# vga_ambilight_throughhole.net
KiCad netlist of a schematic drawn in EAGLE
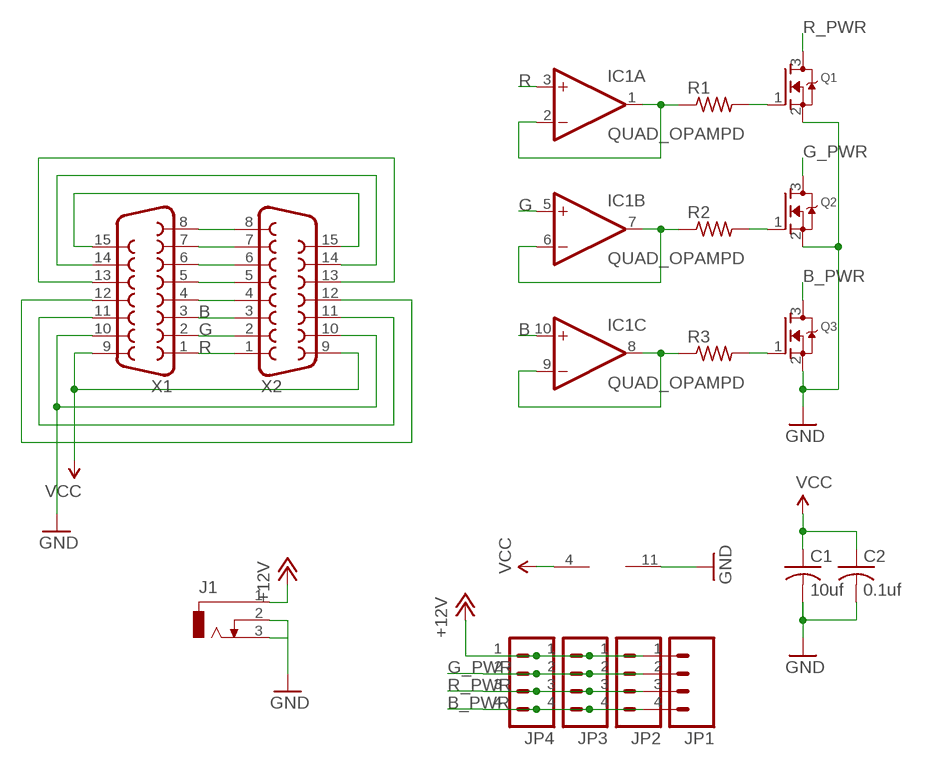
[diagram p0: schematic, sheet 1]

(export (version "E")
  (design (tool "Eeschema 10.0.6"))
  (components
    (comp (ref "C1")
      (value "10uf")
      (footprint "eagle-import:C1206")
      (libsource (lib "eagle-import") (part "C-USC1206"))
    )
    (comp (ref "C2")
      (value "0.1uf")
      (footprint "eagle-import:C1206")
      (libsource (lib "eagle-import") (part "C-USC1206"))
    )
    (comp (ref "IC1")
      (value "QUAD_OPAMPD")
      (footprint "eagle-import:SO14")
      (libsource (lib "eagle-import") (part "QUAD_OPAMPD"))
    )
    (comp (ref "J1")
      (value "DCJ0303")
      (footprint "eagle-import:DCJ0303")
      (libsource (lib "eagle-import") (part "DCJ0303"))
    )
    (comp (ref "JP1")
      (value "M04PTH")
      (footprint "eagle-import:1X04")
      (libsource (lib "eagle-import") (part "M04PTH"))
    )
    (comp (ref "JP2")
      (value "M04PTH")
      (footprint "eagle-import:1X04")
      (libsource (lib "eagle-import") (part "M04PTH"))
    )
    (comp (ref "JP3")
      (value "M04PTH")
      (footprint "eagle-import:1X04")
      (libsource (lib "eagle-import") (part "M04PTH"))
    )
    (comp (ref "JP4")
      (value "M04PTH")
      (footprint "eagle-import:1X04")
      (libsource (lib "eagle-import") (part "M04PTH"))
    )
    (comp (ref "Q1")
      (value "MOSFET-NREFLOW")
      (footprint "eagle-import:SOT23")
      (libsource (lib "eagle-import") (part "MOSFET-NREFLOW"))
    )
    (comp (ref "Q2")
      (value "MOSFET-NREFLOW")
      (footprint "eagle-import:SOT23")
      (libsource (lib "eagle-import") (part "MOSFET-NREFLOW"))
    )
    (comp (ref "Q3")
      (value "MOSFET-NREFLOW")
      (footprint "eagle-import:SOT23")
      (libsource (lib "eagle-import") (part "MOSFET-NREFLOW"))
    )
    (comp (ref "R1")
      (value "R-US_M0805")
      (footprint "eagle-import:M0805")
      (libsource (lib "eagle-import") (part "R-US_M0805"))
    )
    (comp (ref "R2")
      (value "R-US_M0805")
      (footprint "eagle-import:M0805")
      (libsource (lib "eagle-import") (part "R-US_M0805"))
    )
    (comp (ref "R3")
      (value "R-US_M0805")
      (footprint "eagle-import:M0805")
      (libsource (lib "eagle-import") (part "R-US_M0805"))
    )
    (comp (ref "X1")
      (value "F15HP")
      (footprint "eagle-import:F15HP")
      (libsource (lib "eagle-import") (part "F15HP"))
    )
    (comp (ref "X2")
      (value "F15HP")
      (footprint "eagle-import:F15HP")
      (libsource (lib "eagle-import") (part "F15HP"))
    )
  )
  (nets
    (net (code "1") (name "+12V") (class "Default")
      (node (ref "J1") (pin "1") (pinfunction "1_1") (pintype "passive"))
      (node (ref "JP1") (pin "1") (pinfunction "1_1") (pintype "passive"))
      (node (ref "JP2") (pin "1") (pinfunction "1_1") (pintype "passive"))
      (node (ref "JP3") (pin "1") (pinfunction "1_1") (pintype "passive"))
      (node (ref "JP4") (pin "1") (pinfunction "1_1") (pintype "passive"))
    )
    (net (code "2") (name "/B") (class "Default")
      (node (ref "IC1") (pin "10") (pinfunction "+IN_10") (pintype "input"))
      (node (ref "X1") (pin "3") (pinfunction "3_3") (pintype "passive"))
      (node (ref "X2") (pin "3") (pinfunction "3_3") (pintype "passive"))
    )
    (net (code "3") (name "/B_PWR") (class "Default")
      (node (ref "JP1") (pin "4") (pinfunction "4_4") (pintype "passive"))
      (node (ref "JP2") (pin "4") (pinfunction "4_4") (pintype "passive"))
      (node (ref "JP3") (pin "4") (pinfunction "4_4") (pintype "passive"))
      (node (ref "JP4") (pin "4") (pinfunction "4_4") (pintype "passive"))
      (node (ref "Q3") (pin "3") (pinfunction "D_3") (pintype "bidirectional"))
    )
    (net (code "4") (name "/G") (class "Default")
      (node (ref "IC1") (pin "5") (pinfunction "+IN_5") (pintype "input"))
      (node (ref "X1") (pin "2") (pinfunction "2_2") (pintype "passive"))
      (node (ref "X2") (pin "2") (pinfunction "2_2") (pintype "passive"))
    )
    (net (code "5") (name "/G_PWR") (class "Default")
      (node (ref "JP1") (pin "2") (pinfunction "2_2") (pintype "passive"))
      (node (ref "JP2") (pin "2") (pinfunction "2_2") (pintype "passive"))
      (node (ref "JP3") (pin "2") (pinfunction "2_2") (pintype "passive"))
      (node (ref "JP4") (pin "2") (pinfunction "2_2") (pintype "passive"))
      (node (ref "Q2") (pin "3") (pinfunction "D_3") (pintype "bidirectional"))
    )
    (net (code "6") (name "/R") (class "Default")
      (node (ref "IC1") (pin "3") (pinfunction "+IN_3") (pintype "input"))
      (node (ref "X1") (pin "1") (pinfunction "1_1") (pintype "passive"))
      (node (ref "X2") (pin "1") (pinfunction "1_1") (pintype "passive"))
    )
    (net (code "7") (name "/R_PWR") (class "Default")
      (node (ref "JP1") (pin "3") (pinfunction "3_3") (pintype "passive"))
      (node (ref "JP2") (pin "3") (pinfunction "3_3") (pintype "passive"))
      (node (ref "JP3") (pin "3") (pinfunction "3_3") (pintype "passive"))
      (node (ref "JP4") (pin "3") (pinfunction "3_3") (pintype "passive"))
      (node (ref "Q1") (pin "3") (pinfunction "D_3") (pintype "bidirectional"))
    )
    (net (code "8") (name "GND") (class "Default")
      (node (ref "C1") (pin "2") (pinfunction "2_2") (pintype "passive"))
      (node (ref "C2") (pin "2") (pinfunction "2_2") (pintype "passive"))
      (node (ref "IC1") (pin "11") (pinfunction "V-_11") (pintype "power_in"))
      (node (ref "J1") (pin "2") (pinfunction "2_2") (pintype "passive"))
      (node (ref "J1") (pin "3") (pinfunction "3_3") (pintype "passive"))
      (node (ref "Q1") (pin "2") (pinfunction "S_2") (pintype "bidirectional"))
      (node (ref "Q2") (pin "2") (pinfunction "S_2") (pintype "bidirectional"))
      (node (ref "Q3") (pin "2") (pinfunction "S_2") (pintype "bidirectional"))
      (node (ref "X1") (pin "10") (pinfunction "10_10") (pintype "passive"))
      (node (ref "X2") (pin "10") (pinfunction "10_10") (pintype "passive"))
    )
    (net (code "9") (name "Net-(IC1A--IN)") (class "Default")
      (node (ref "IC1") (pin "1") (pinfunction "OUT_1") (pintype "output"))
      (node (ref "IC1") (pin "2") (pinfunction "-IN_2") (pintype "input"))
      (node (ref "R1") (pin "1") (pinfunction "1_1") (pintype "passive"))
    )
    (net (code "10") (name "Net-(IC1B--IN)") (class "Default")
      (node (ref "IC1") (pin "6") (pinfunction "-IN_6") (pintype "input"))
      (node (ref "IC1") (pin "7") (pinfunction "OUT_7") (pintype "output"))
      (node (ref "R2") (pin "1") (pinfunction "1_1") (pintype "passive"))
    )
    (net (code "11") (name "Net-(IC1C--IN)") (class "Default")
      (node (ref "IC1") (pin "8") (pinfunction "OUT_8") (pintype "output"))
      (node (ref "IC1") (pin "9") (pinfunction "-IN_9") (pintype "input"))
      (node (ref "R3") (pin "1") (pinfunction "1_1") (pintype "passive"))
    )
    (net (code "12") (name "Net-(Q1-G)") (class "Default")
      (node (ref "Q1") (pin "1") (pinfunction "G_1") (pintype "bidirectional"))
      (node (ref "R1") (pin "2") (pinfunction "2_2") (pintype "passive"))
    )
    (net (code "13") (name "Net-(Q2-G)") (class "Default")
      (node (ref "Q2") (pin "1") (pinfunction "G_1") (pintype "bidirectional"))
      (node (ref "R2") (pin "2") (pinfunction "2_2") (pintype "passive"))
    )
    (net (code "14") (name "Net-(Q3-G)") (class "Default")
      (node (ref "Q3") (pin "1") (pinfunction "G_1") (pintype "bidirectional"))
      (node (ref "R3") (pin "2") (pinfunction "2_2") (pintype "passive"))
    )
    (net (code "15") (name "Net-(X1-Pad4)") (class "Default")
      (node (ref "X1") (pin "4") (pinfunction "4_4") (pintype "passive"))
      (node (ref "X2") (pin "4") (pinfunction "4_4") (pintype "passive"))
    )
    (net (code "16") (name "Net-(X1-Pad5)") (class "Default")
      (node (ref "X1") (pin "5") (pinfunction "5_5") (pintype "passive"))
      (node (ref "X2") (pin "5") (pinfunction "5_5") (pintype "passive"))
    )
    (net (code "17") (name "Net-(X1-Pad6)") (class "Default")
      (node (ref "X1") (pin "6") (pinfunction "6_6") (pintype "passive"))
      (node (ref "X2") (pin "6") (pinfunction "6_6") (pintype "passive"))
    )
    (net (code "18") (name "Net-(X1-Pad7)") (class "Default")
      (node (ref "X1") (pin "7") (pinfunction "7_7") (pintype "passive"))
      (node (ref "X2") (pin "7") (pinfunction "7_7") (pintype "passive"))
    )
    (net (code "19") (name "Net-(X1-Pad8)") (class "Default")
      (node (ref "X1") (pin "8") (pinfunction "8_8") (pintype "passive"))
      (node (ref "X2") (pin "8") (pinfunction "8_8") (pintype "passive"))
    )
    (net (code "20") (name "Net-(X1-Pad11)") (class "Default")
      (node (ref "X1") (pin "11") (pinfunction "11_11") (pintype "passive"))
      (node (ref "X2") (pin "11") (pinfunction "11_11") (pintype "passive"))
    )
    (net (code "21") (name "Net-(X1-Pad12)") (class "Default")
      (node (ref "X1") (pin "12") (pinfunction "12_12") (pintype "passive"))
      (node (ref "X2") (pin "12") (pinfunction "12_12") (pintype "passive"))
    )
    (net (code "22") (name "Net-(X1-Pad13)") (class "Default")
      (node (ref "X1") (pin "13") (pinfunction "13_13") (pintype "passive"))
      (node (ref "X2") (pin "13") (pinfunction "13_13") (pintype "passive"))
    )
    (net (code "23") (name "Net-(X1-Pad14)") (class "Default")
      (node (ref "X1") (pin "14") (pinfunction "14_14") (pintype "passive"))
      (node (ref "X2") (pin "14") (pinfunction "14_14") (pintype "passive"))
    )
    (net (code "24") (name "Net-(X1-Pad15)") (class "Default")
      (node (ref "X1") (pin "15") (pinfunction "15_15") (pintype "passive"))
      (node (ref "X2") (pin "15") (pinfunction "15_15") (pintype "passive"))
    )
    (net (code "25") (name "VCC") (class "Default")
      (node (ref "C1") (pin "1") (pinfunction "1_1") (pintype "passive"))
      (node (ref "C2") (pin "1") (pinfunction "1_1") (pintype "passive"))
      (node (ref "IC1") (pin "4") (pinfunction "V+_4") (pintype "power_in"))
      (node (ref "X1") (pin "9") (pinfunction "9_9") (pintype "passive"))
      (node (ref "X2") (pin "9") (pinfunction "9_9") (pintype "passive"))
    )
  )
)
